# B0_DC12_DC51_1.net
KiCad netlist of a schematic drawn in EAGLE
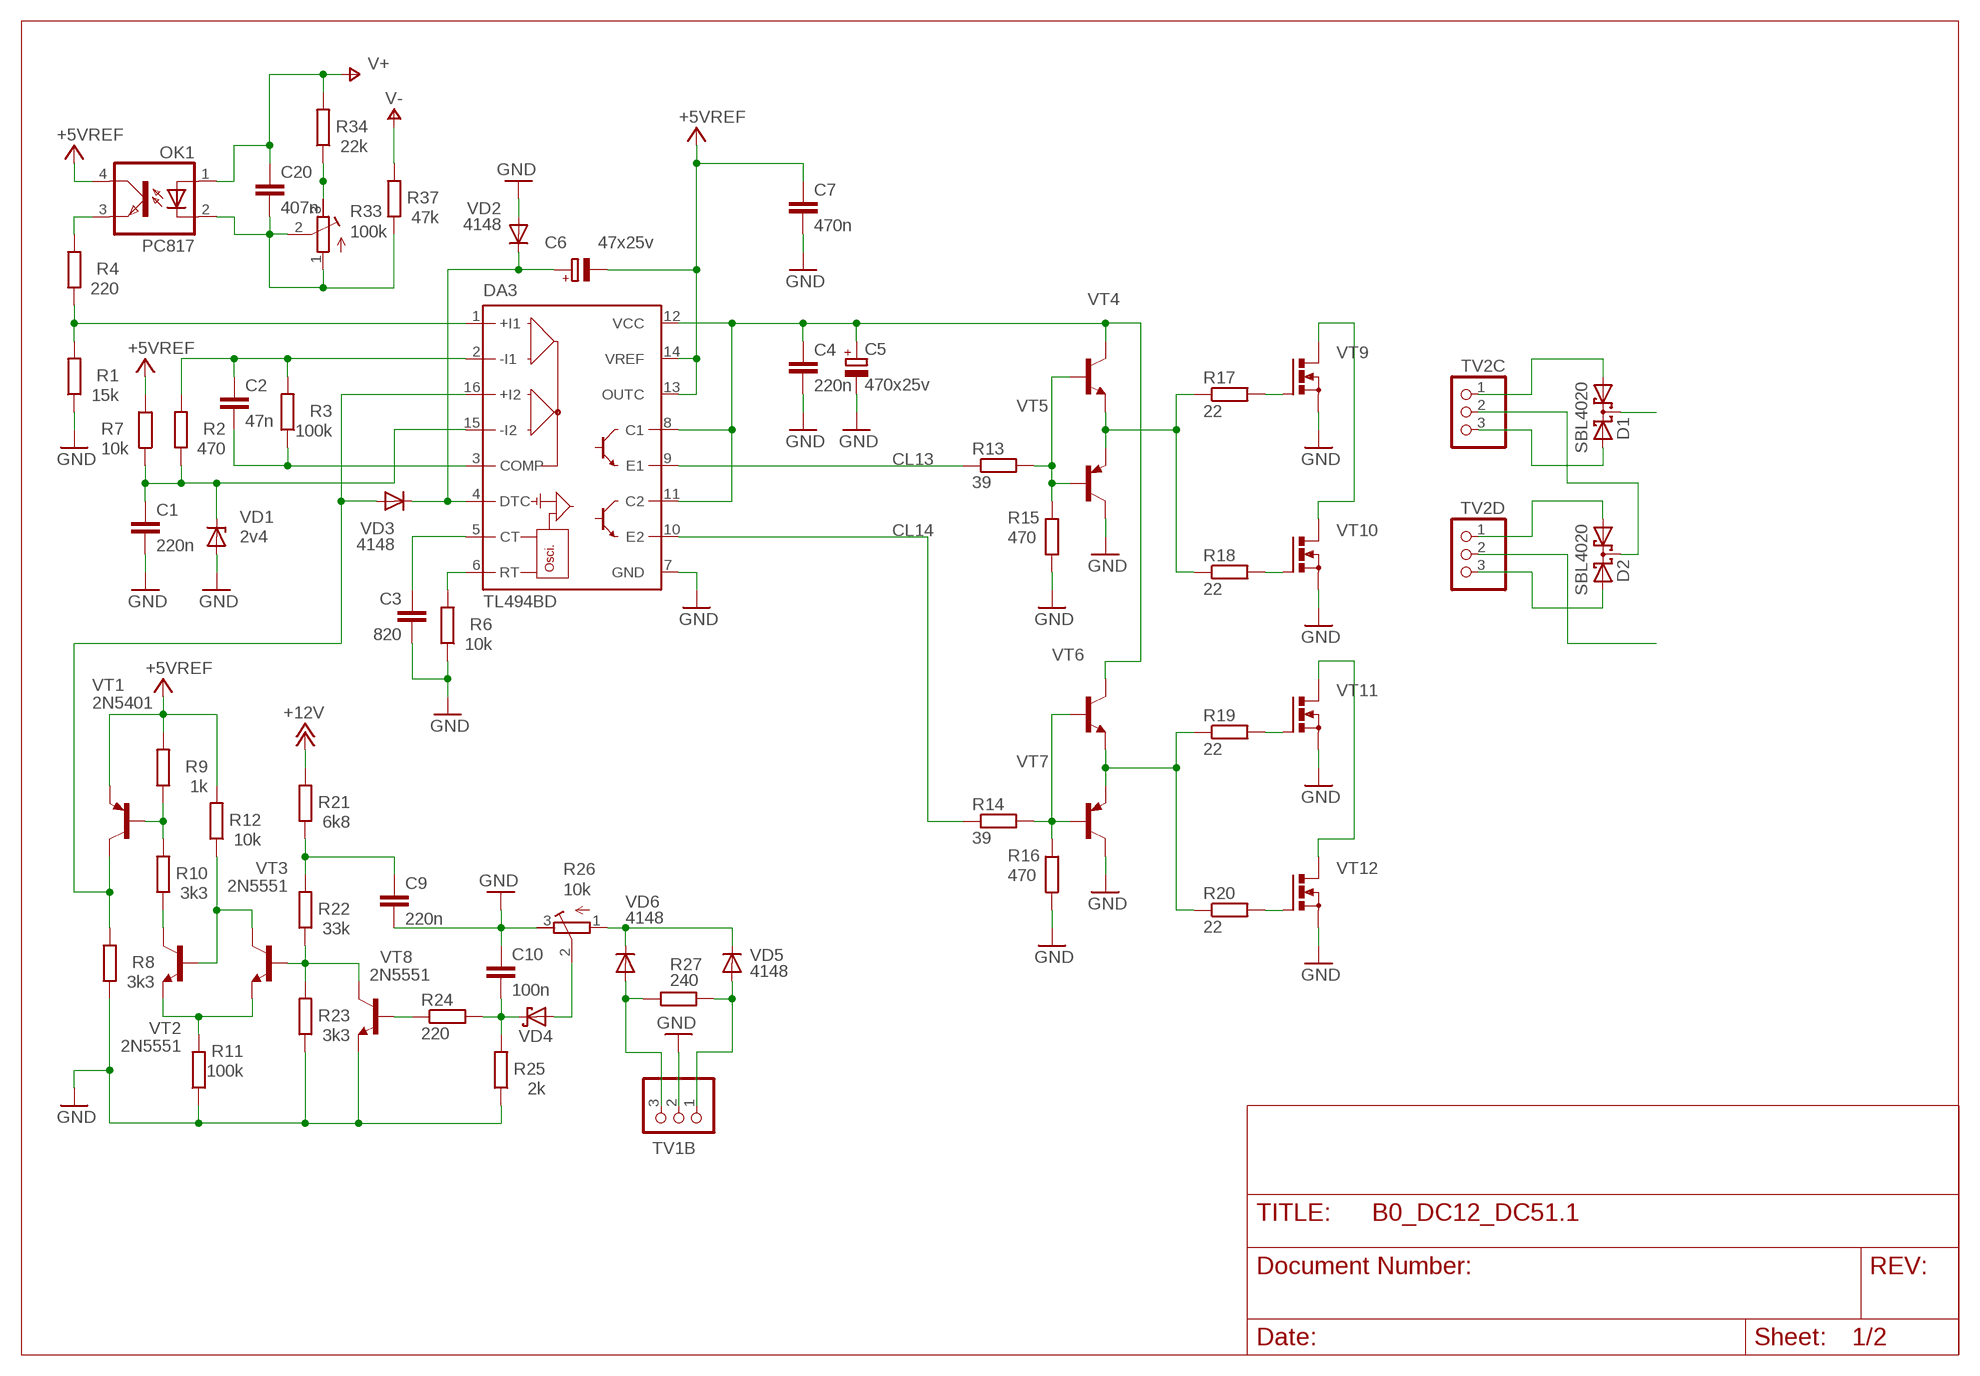
[diagram p0: schematic, sheet 1]
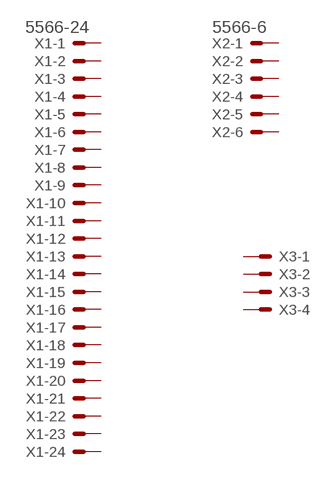
[diagram p1: schematic, sheet 2]

(export (version "E")
  (design (tool "Eeschema 10.0.6"))
  (components
    (comp (ref "X1")
      (value "5566-24")
      (footprint "eagle-import:5566-24")
      (libsource (lib "eagle-import") (part "5566-24"))
    )
    (comp (ref "X2")
      (value "5566-6")
      (footprint "eagle-import:5566-6")
      (fields (field (name "MPN") "95566-61002"))
      (libsource (lib "eagle-import") (part "5566-6"))
    )
    (comp (ref "X3")
      (value "KK-156-4")
      (footprint "eagle-import:KK-156-4")
      (libsource (lib "eagle-import") (part "KK-156-4"))
    )
    (comp (ref "C1")
      (value "220n")
      (footprint "eagle-import:C0805")
      (libsource (lib "eagle-import") (part "C-EUC0805"))
    )
    (comp (ref "C2")
      (value "47n")
      (footprint "eagle-import:C0805")
      (libsource (lib "eagle-import") (part "C-EUC0805"))
    )
    (comp (ref "C3")
      (value "820")
      (footprint "eagle-import:C025-025X050")
      (libsource (lib "eagle-import") (part "C-EU025-025X050"))
    )
    (comp (ref "C4")
      (value "220n")
      (footprint "eagle-import:C0805")
      (libsource (lib "eagle-import") (part "C-EUC0805"))
    )
    (comp (ref "C5")
      (value "470x25v")
      (footprint "eagle-import:E5-10,5")
      (libsource (lib "eagle-import") (part "CPOL-EUE5-10.5"))
    )
    (comp (ref "C6")
      (value "47x25v")
      (footprint "eagle-import:E5-10,5")
      (libsource (lib "eagle-import") (part "CPOL-EUE5-10.5"))
    )
    (comp (ref "C7")
      (value "470n")
      (footprint "eagle-import:C0805")
      (libsource (lib "eagle-import") (part "C-EUC0805"))
    )
    (comp (ref "C9")
      (value "220n")
      (footprint "eagle-import:C0805")
      (libsource (lib "eagle-import") (part "C-EUC0805"))
    )
    (comp (ref "C10")
      (value "100n")
      (footprint "eagle-import:C0805")
      (libsource (lib "eagle-import") (part "C-EUC0805"))
    )
    (comp (ref "C20")
      (value "407n")
      (footprint "eagle-import:C0805")
      (libsource (lib "eagle-import") (part "C-EUC0805"))
    )
    (comp (ref "D1")
      (value "SBL4020")
      (footprint "eagle-import:TO247H")
      (libsource (lib "eagle-import") (part "SCHOTTKY_DUALTO247H"))
    )
    (comp (ref "D2")
      (value "SBL4020")
      (footprint "eagle-import:TO247H")
      (libsource (lib "eagle-import") (part "SCHOTTKY_DUALTO247H"))
    )
    (comp (ref "DA3")
      (value "TL494BD")
      (footprint "eagle-import:SO16")
      (libsource (lib "eagle-import") (part "TL494DB"))
    )
    (comp (ref "OK1")
      (value "PC817")
      (footprint "eagle-import:DIL04")
      (fields (field (name "MPN") "PC817X4J000F"))
      (libsource (lib "eagle-import") (part "PC817"))
    )
    (comp (ref "R1")
      (value "15k")
      (footprint "eagle-import:M0805")
      (libsource (lib "eagle-import") (part "R-EU_M0805"))
    )
    (comp (ref "R2")
      (value "470")
      (footprint "eagle-import:M0805")
      (libsource (lib "eagle-import") (part "R-EU_M0805"))
    )
    (comp (ref "R3")
      (value "100k")
      (footprint "eagle-import:R0805")
      (libsource (lib "eagle-import") (part "R-EU_R0805"))
    )
    (comp (ref "R4")
      (value "220")
      (footprint "eagle-import:M0805")
      (libsource (lib "eagle-import") (part "R-EU_M0805"))
    )
    (comp (ref "R6")
      (value "10k")
      (footprint "eagle-import:0207_12")
      (libsource (lib "eagle-import") (part "R-EU_0207/12"))
    )
    (comp (ref "R7")
      (value "10k")
      (footprint "eagle-import:M0805")
      (libsource (lib "eagle-import") (part "R-EU_M0805"))
    )
    (comp (ref "R8")
      (value "3k3")
      (footprint "eagle-import:M0805")
      (libsource (lib "eagle-import") (part "R-EU_M0805"))
    )
    (comp (ref "R9")
      (value "1k")
      (footprint "eagle-import:M0805")
      (libsource (lib "eagle-import") (part "R-EU_M0805"))
    )
    (comp (ref "R10")
      (value "3k3")
      (footprint "eagle-import:M0805")
      (libsource (lib "eagle-import") (part "R-EU_M0805"))
    )
    (comp (ref "R11")
      (value "100k")
      (footprint "eagle-import:M0805")
      (libsource (lib "eagle-import") (part "R-EU_M0805"))
    )
    (comp (ref "R12")
      (value "10k")
      (footprint "eagle-import:M0805")
      (libsource (lib "eagle-import") (part "R-EU_M0805"))
    )
    (comp (ref "R13")
      (value "39")
      (footprint "eagle-import:M0805")
      (libsource (lib "eagle-import") (part "R-EU_M0805"))
    )
    (comp (ref "R14")
      (value "39")
      (footprint "eagle-import:M0805")
      (libsource (lib "eagle-import") (part "R-EU_M0805"))
    )
    (comp (ref "R15")
      (value "470")
      (footprint "eagle-import:M0805")
      (libsource (lib "eagle-import") (part "R-EU_M0805"))
    )
    (comp (ref "R16")
      (value "470")
      (footprint "eagle-import:M0805")
      (libsource (lib "eagle-import") (part "R-EU_M0805"))
    )
    (comp (ref "R17")
      (value "22")
      (footprint "eagle-import:M0805")
      (libsource (lib "eagle-import") (part "R-EU_M0805"))
    )
    (comp (ref "R18")
      (value "22")
      (footprint "eagle-import:M0805")
      (libsource (lib "eagle-import") (part "R-EU_M0805"))
    )
    (comp (ref "R19")
      (value "22")
      (footprint "eagle-import:M0805")
      (libsource (lib "eagle-import") (part "R-EU_M0805"))
    )
    (comp (ref "R20")
      (value "22")
      (footprint "eagle-import:M0805")
      (libsource (lib "eagle-import") (part "R-EU_M0805"))
    )
    (comp (ref "R21")
      (value "6k8")
      (footprint "eagle-import:M0805")
      (libsource (lib "eagle-import") (part "R-EU_M0805"))
    )
    (comp (ref "R22")
      (value "33k")
      (footprint "eagle-import:M0805")
      (libsource (lib "eagle-import") (part "R-EU_M0805"))
    )
    (comp (ref "R23")
      (value "3k3")
      (footprint "eagle-import:M0805")
      (libsource (lib "eagle-import") (part "R-EU_M0805"))
    )
    (comp (ref "R24")
      (value "220")
      (footprint "eagle-import:M0805")
      (libsource (lib "eagle-import") (part "R-EU_M0805"))
    )
    (comp (ref "R25")
      (value "2k")
      (footprint "eagle-import:M0805")
      (libsource (lib "eagle-import") (part "R-EU_M0805"))
    )
    (comp (ref "R26")
      (value "10k")
      (footprint "eagle-import:RTRIM3296W")
      (libsource (lib "eagle-import") (part "R-TRIMM3296W"))
    )
    (comp (ref "R27")
      (value "240")
      (footprint "eagle-import:0207_10")
      (libsource (lib "eagle-import") (part "R-EU_0207/10"))
    )
    (comp (ref "R33")
      (value "100k")
      (footprint "eagle-import:RTRIM3296W")
      (libsource (lib "eagle-import") (part "R-TRIMM3296W"))
    )
    (comp (ref "R34")
      (value "22k")
      (footprint "eagle-import:M0805")
      (libsource (lib "eagle-import") (part "R-EU_M0805"))
    )
    (comp (ref "R37")
      (value "47k")
      (footprint "eagle-import:M0805")
      (libsource (lib "eagle-import") (part "R-EU_M0805"))
    )
    (comp (ref "TV1B")
      (value "PINHD-1X3")
      (footprint "eagle-import:1X03")
      (libsource (lib "eagle-import") (part "PINHD-1X3"))
    )
    (comp (ref "TV2C")
      (value "PINHD-1X3")
      (footprint "eagle-import:1X03")
      (libsource (lib "eagle-import") (part "PINHD-1X3"))
    )
    (comp (ref "TV2D")
      (value "PINHD-1X3")
      (footprint "eagle-import:1X03")
      (libsource (lib "eagle-import") (part "PINHD-1X3"))
    )
    (comp (ref "VD1")
      (value "2v4")
      (footprint "eagle-import:SOD80C")
      (libsource (lib "eagle-import") (part "ZENER-DIODESOD80C"))
    )
    (comp (ref "VD2")
      (value "4148")
      (footprint "eagle-import:SOD80C")
      (libsource (lib "eagle-import") (part "DIODE-SOD80C"))
    )
    (comp (ref "VD3")
      (value "4148")
      (footprint "eagle-import:SOD80C")
      (libsource (lib "eagle-import") (part "DIODE-SOD80C"))
    )
    (comp (ref "VD4")
      (value "1N5817-B")
      (footprint "eagle-import:DO41-7.6")
      (libsource (lib "eagle-import") (part "1N5817-B"))
    )
    (comp (ref "VD5")
      (value "4148")
      (footprint "eagle-import:SOD80C")
      (libsource (lib "eagle-import") (part "DIODE-SOD80C"))
    )
    (comp (ref "VD6")
      (value "4148")
      (footprint "eagle-import:SOD80C")
      (libsource (lib "eagle-import") (part "DIODE-SOD80C"))
    )
    (comp (ref "VT1")
      (value "2N5401")
      (footprint "eagle-import:TO92")
      (libsource (lib "eagle-import") (part "BJT_PNP_TO-92_ECB"))
    )
    (comp (ref "VT2")
      (value "2N5551")
      (footprint "eagle-import:TO92")
      (libsource (lib "eagle-import") (part "BJT_NPN_TO-92_ECB"))
    )
    (comp (ref "VT3")
      (value "2N5551")
      (footprint "eagle-import:TO92")
      (libsource (lib "eagle-import") (part "BJT_NPN_TO-92_ECB"))
    )
    (comp (ref "VT4")
      (value "-NPN-TO126V")
      (footprint "eagle-import:TO126V")
      (libsource (lib "eagle-import") (part "-NPN-TO126V"))
    )
    (comp (ref "VT5")
      (value "-PNP-TO126V")
      (footprint "eagle-import:TO126V")
      (libsource (lib "eagle-import") (part "-PNP-TO126V"))
    )
    (comp (ref "VT6")
      (value "-NPN-TO126V")
      (footprint "eagle-import:TO126V")
      (libsource (lib "eagle-import") (part "-NPN-TO126V"))
    )
    (comp (ref "VT7")
      (value "-PNP-TO126V")
      (footprint "eagle-import:TO126V")
      (libsource (lib "eagle-import") (part "-PNP-TO126V"))
    )
    (comp (ref "VT8")
      (value "2N5551")
      (footprint "eagle-import:TO92")
      (libsource (lib "eagle-import") (part "BJT_NPN_TO-92_ECB"))
    )
    (comp (ref "VT9")
      (value "MOSFET-N_DPACK")
      (footprint "eagle-import:DPACK")
      (libsource (lib "eagle-import") (part "MOSFET-N_DPACK"))
    )
    (comp (ref "VT10")
      (value "MOSFET-N_DPACK")
      (footprint "eagle-import:DPACK")
      (libsource (lib "eagle-import") (part "MOSFET-N_DPACK"))
    )
    (comp (ref "VT11")
      (value "MOSFET-N_DPACK")
      (footprint "eagle-import:DPACK")
      (libsource (lib "eagle-import") (part "MOSFET-N_DPACK"))
    )
    (comp (ref "VT12")
      (value "MOSFET-N_DPACK")
      (footprint "eagle-import:DPACK")
      (libsource (lib "eagle-import") (part "MOSFET-N_DPACK"))
    )
  )
  (nets
    (net (code "1") (name "+5VREF") (class "Default")
      (node (ref "C6") (pin "-") (pinfunction "-_-") (pintype "passive"))
      (node (ref "C7") (pin "1") (pinfunction "1_1") (pintype "passive"))
      (node (ref "DA3") (pin "13") (pinfunction "OUTC_13") (pintype "output"))
      (node (ref "DA3") (pin "14") (pinfunction "VREF_14") (pintype "input"))
      (node (ref "OK1") (pin "4") (pinfunction "COL_4") (pintype "passive"))
      (node (ref "R12") (pin "2") (pinfunction "2_2") (pintype "passive"))
      (node (ref "R7") (pin "2") (pinfunction "2_2") (pintype "passive"))
      (node (ref "R9") (pin "2") (pinfunction "2_2") (pintype "passive"))
      (node (ref "VT1") (pin "1") (pinfunction "E_1") (pintype "passive"))
    )
    (net (code "2") (name "+12V") (class "Default")
      (node (ref "R21") (pin "2") (pinfunction "2_2") (pintype "passive"))
    )
    (net (code "3") (name "CL13") (class "Default")
      (node (ref "DA3") (pin "9") (pinfunction "E1_9") (pintype "passive"))
      (node (ref "R13") (pin "1") (pinfunction "1_1") (pintype "passive"))
    )
    (net (code "4") (name "CL14") (class "Default")
      (node (ref "DA3") (pin "10") (pinfunction "E2_10") (pintype "passive"))
      (node (ref "R14") (pin "1") (pinfunction "1_1") (pintype "passive"))
    )
    (net (code "5") (name "GND") (class "Default")
      (node (ref "C1") (pin "2") (pinfunction "2_2") (pintype "passive"))
      (node (ref "C10") (pin "1") (pinfunction "1_1") (pintype "passive"))
      (node (ref "C3") (pin "2") (pinfunction "2_2") (pintype "passive"))
      (node (ref "C4") (pin "2") (pinfunction "2_2") (pintype "passive"))
      (node (ref "C5") (pin "-") (pinfunction "-_-") (pintype "passive"))
      (node (ref "C7") (pin "2") (pinfunction "2_2") (pintype "passive"))
      (node (ref "C9") (pin "2") (pinfunction "2_2") (pintype "passive"))
      (node (ref "DA3") (pin "7") (pinfunction "GND_7") (pintype "power_in"))
      (node (ref "R1") (pin "1") (pinfunction "1_1") (pintype "passive"))
      (node (ref "R11") (pin "1") (pinfunction "1_1") (pintype "passive"))
      (node (ref "R15") (pin "1") (pinfunction "1_1") (pintype "passive"))
      (node (ref "R16") (pin "1") (pinfunction "1_1") (pintype "passive"))
      (node (ref "R23") (pin "1") (pinfunction "1_1") (pintype "passive"))
      (node (ref "R25") (pin "1") (pinfunction "1_1") (pintype "passive"))
      (node (ref "R26") (pin "3") (pinfunction "E_3") (pintype "passive"))
      (node (ref "R6") (pin "1") (pinfunction "1_1") (pintype "passive"))
      (node (ref "R8") (pin "1") (pinfunction "1_1") (pintype "passive"))
      (node (ref "TV1B") (pin "2") (pinfunction "2_2") (pintype "passive"))
      (node (ref "VD1") (pin "A") (pinfunction "A_A") (pintype "passive"))
      (node (ref "VD2") (pin "A") (pinfunction "A_A") (pintype "passive"))
      (node (ref "VT10") (pin "S") (pinfunction "S_S") (pintype "passive"))
      (node (ref "VT11") (pin "S") (pinfunction "S_S") (pintype "passive"))
      (node (ref "VT12") (pin "S") (pinfunction "S_S") (pintype "passive"))
      (node (ref "VT5") (pin "2") (pinfunction "C_2") (pintype "passive"))
      (node (ref "VT7") (pin "2") (pinfunction "C_2") (pintype "passive"))
      (node (ref "VT8") (pin "1") (pinfunction "E_1") (pintype "passive"))
      (node (ref "VT9") (pin "S") (pinfunction "S_S") (pintype "passive"))
    )
    (net (code "6") (name "Net-(C9-Pad1)") (class "Default")
      (node (ref "C9") (pin "1") (pinfunction "1_1") (pintype "passive"))
      (node (ref "R21") (pin "1") (pinfunction "1_1") (pintype "passive"))
      (node (ref "R22") (pin "2") (pinfunction "2_2") (pintype "passive"))
    )
    (net (code "7") (name "Net-(C10-Pad2)") (class "Default")
      (node (ref "C10") (pin "2") (pinfunction "2_2") (pintype "passive"))
      (node (ref "R24") (pin "2") (pinfunction "2_2") (pintype "passive"))
      (node (ref "R25") (pin "2") (pinfunction "2_2") (pintype "passive"))
      (node (ref "VD4") (pin "C") (pinfunction "C_C") (pintype "passive"))
    )
    (net (code "8") (name "Net-(D1-A1)") (class "Default")
      (node (ref "D1") (pin "1") (pinfunction "A1_1") (pintype "passive"))
      (node (ref "TV2C") (pin "1") (pinfunction "1_1") (pintype "passive"))
    )
    (net (code "9") (name "Net-(D1-A2)") (class "Default")
      (node (ref "D1") (pin "3") (pinfunction "A2_3") (pintype "passive"))
      (node (ref "TV2C") (pin "3") (pinfunction "3_3") (pintype "passive"))
    )
    (net (code "10") (name "Net-(D2-A1)") (class "Default")
      (node (ref "D2") (pin "1") (pinfunction "A1_1") (pintype "passive"))
      (node (ref "TV2D") (pin "1") (pinfunction "1_1") (pintype "passive"))
    )
    (net (code "11") (name "Net-(D2-A2)") (class "Default")
      (node (ref "D2") (pin "3") (pinfunction "A2_3") (pintype "passive"))
      (node (ref "TV2D") (pin "3") (pinfunction "3_3") (pintype "passive"))
    )
    (net (code "12") (name "Net-(D2-C)") (class "Default")
      (node (ref "D2") (pin "2") (pinfunction "C_2") (pintype "passive"))
      (node (ref "TV2C") (pin "2") (pinfunction "2_2") (pintype "passive"))
    )
    (net (code "13") (name "Net-(DA3-+I1)") (class "Default")
      (node (ref "DA3") (pin "1") (pinfunction "+I1_1") (pintype "input"))
      (node (ref "R1") (pin "2") (pinfunction "2_2") (pintype "passive"))
      (node (ref "R4") (pin "1") (pinfunction "1_1") (pintype "passive"))
    )
    (net (code "14") (name "Net-(DA3-+I2)") (class "Default")
      (node (ref "DA3") (pin "16") (pinfunction "+I2_16") (pintype "input"))
      (node (ref "R8") (pin "2") (pinfunction "2_2") (pintype "passive"))
      (node (ref "VD3") (pin "A") (pinfunction "A_A") (pintype "passive"))
      (node (ref "VT1") (pin "2") (pinfunction "C_2") (pintype "passive"))
    )
    (net (code "15") (name "Net-(DA3--I1)") (class "Default")
      (node (ref "C2") (pin "1") (pinfunction "1_1") (pintype "passive"))
      (node (ref "DA3") (pin "2") (pinfunction "-I1_2") (pintype "input"))
      (node (ref "R2") (pin "2") (pinfunction "2_2") (pintype "passive"))
      (node (ref "R3") (pin "2") (pinfunction "2_2") (pintype "passive"))
    )
    (net (code "16") (name "Net-(DA3--I2)") (class "Default")
      (node (ref "C1") (pin "1") (pinfunction "1_1") (pintype "passive"))
      (node (ref "DA3") (pin "15") (pinfunction "-I2_15") (pintype "input"))
      (node (ref "R2") (pin "1") (pinfunction "1_1") (pintype "passive"))
      (node (ref "R7") (pin "1") (pinfunction "1_1") (pintype "passive"))
      (node (ref "VD1") (pin "C") (pinfunction "C_C") (pintype "passive"))
    )
    (net (code "17") (name "Net-(DA3-C1)") (class "Default")
      (node (ref "C4") (pin "1") (pinfunction "1_1") (pintype "passive"))
      (node (ref "C5") (pin "+") (pinfunction "+_+") (pintype "passive"))
      (node (ref "DA3") (pin "11") (pinfunction "C2_11") (pintype "passive"))
      (node (ref "DA3") (pin "12") (pinfunction "VCC_12") (pintype "power_in"))
      (node (ref "DA3") (pin "8") (pinfunction "C1_8") (pintype "passive"))
      (node (ref "VT4") (pin "2") (pinfunction "C_2") (pintype "passive"))
      (node (ref "VT6") (pin "2") (pinfunction "C_2") (pintype "passive"))
    )
    (net (code "18") (name "Net-(DA3-COMP)") (class "Default")
      (node (ref "C2") (pin "2") (pinfunction "2_2") (pintype "passive"))
      (node (ref "DA3") (pin "3") (pinfunction "COMP_3") (pintype "passive"))
      (node (ref "R3") (pin "1") (pinfunction "1_1") (pintype "passive"))
    )
    (net (code "19") (name "Net-(DA3-CT)") (class "Default")
      (node (ref "C3") (pin "1") (pinfunction "1_1") (pintype "passive"))
      (node (ref "DA3") (pin "5") (pinfunction "CT_5") (pintype "input"))
    )
    (net (code "20") (name "Net-(DA3-DTC)") (class "Default")
      (node (ref "C6") (pin "+") (pinfunction "+_+") (pintype "passive"))
      (node (ref "DA3") (pin "4") (pinfunction "DTC_4") (pintype "input"))
      (node (ref "VD2") (pin "C") (pinfunction "C_C") (pintype "passive"))
      (node (ref "VD3") (pin "C") (pinfunction "C_C") (pintype "passive"))
    )
    (net (code "21") (name "Net-(DA3-RT)") (class "Default")
      (node (ref "DA3") (pin "6") (pinfunction "RT_6") (pintype "input"))
      (node (ref "R6") (pin "2") (pinfunction "2_2") (pintype "passive"))
    )
    (net (code "22") (name "Net-(OK1-C)") (class "Default")
      (node (ref "C20") (pin "2") (pinfunction "2_2") (pintype "passive"))
      (node (ref "OK1") (pin "2") (pinfunction "C_2") (pintype "passive"))
      (node (ref "R33") (pin "1") (pinfunction "A_1") (pintype "passive"))
      (node (ref "R33") (pin "2") (pinfunction "S_2") (pintype "passive"))
      (node (ref "R37") (pin "1") (pinfunction "1_1") (pintype "passive"))
    )
    (net (code "23") (name "Net-(OK1-EMIT)") (class "Default")
      (node (ref "OK1") (pin "3") (pinfunction "EMIT_3") (pintype "passive"))
      (node (ref "R4") (pin "2") (pinfunction "2_2") (pintype "passive"))
    )
    (net (code "24") (name "Net-(R17-Pad2)") (class "Default")
      (node (ref "R17") (pin "2") (pinfunction "2_2") (pintype "passive"))
      (node (ref "VT9") (pin "G") (pinfunction "G_G") (pintype "passive"))
    )
    (net (code "25") (name "Net-(R18-Pad2)") (class "Default")
      (node (ref "R18") (pin "2") (pinfunction "2_2") (pintype "passive"))
      (node (ref "VT10") (pin "G") (pinfunction "G_G") (pintype "passive"))
    )
    (net (code "26") (name "Net-(R19-Pad2)") (class "Default")
      (node (ref "R19") (pin "2") (pinfunction "2_2") (pintype "passive"))
      (node (ref "VT11") (pin "G") (pinfunction "G_G") (pintype "passive"))
    )
    (net (code "27") (name "Net-(R20-Pad2)") (class "Default")
      (node (ref "R20") (pin "2") (pinfunction "2_2") (pintype "passive"))
      (node (ref "VT12") (pin "G") (pinfunction "G_G") (pintype "passive"))
    )
    (net (code "28") (name "Net-(R26-A)") (class "Default")
      (node (ref "R26") (pin "1") (pinfunction "A_1") (pintype "passive"))
      (node (ref "VD5") (pin "C") (pinfunction "C_C") (pintype "passive"))
      (node (ref "VD6") (pin "C") (pinfunction "C_C") (pintype "passive"))
    )
    (net (code "29") (name "Net-(R26-S)") (class "Default")
      (node (ref "R26") (pin "2") (pinfunction "S_2") (pintype "passive"))
      (node (ref "VD4") (pin "A") (pinfunction "A_A") (pintype "passive"))
    )
    (net (code "30") (name "Net-(R27-Pad1)") (class "Default")
      (node (ref "R27") (pin "1") (pinfunction "1_1") (pintype "passive"))
      (node (ref "TV1B") (pin "3") (pinfunction "3_3") (pintype "passive"))
      (node (ref "VD6") (pin "A") (pinfunction "A_A") (pintype "passive"))
    )
    (net (code "31") (name "Net-(R27-Pad2)") (class "Default")
      (node (ref "R27") (pin "2") (pinfunction "2_2") (pintype "passive"))
      (node (ref "TV1B") (pin "1") (pinfunction "1_1") (pintype "passive"))
      (node (ref "VD5") (pin "A") (pinfunction "A_A") (pintype "passive"))
    )
    (net (code "32") (name "Net-(R33-E)") (class "Default")
      (node (ref "R33") (pin "3") (pinfunction "E_3") (pintype "passive"))
      (node (ref "R34") (pin "1") (pinfunction "1_1") (pintype "passive"))
    )
    (net (code "33") (name "Net-(VT1-B)") (class "Default")
      (node (ref "R10") (pin "2") (pinfunction "2_2") (pintype "passive"))
      (node (ref "R9") (pin "1") (pinfunction "1_1") (pintype "passive"))
      (node (ref "VT1") (pin "3") (pinfunction "B_3") (pintype "passive"))
    )
    (net (code "34") (name "Net-(VT2-B)") (class "Default")
      (node (ref "R12") (pin "1") (pinfunction "1_1") (pintype "passive"))
      (node (ref "VT2") (pin "3") (pinfunction "B_3") (pintype "passive"))
      (node (ref "VT3") (pin "2") (pinfunction "C_2") (pintype "passive"))
    )
    (net (code "35") (name "Net-(VT2-C)") (class "Default")
      (node (ref "R10") (pin "1") (pinfunction "1_1") (pintype "passive"))
      (node (ref "VT2") (pin "2") (pinfunction "C_2") (pintype "passive"))
    )
    (net (code "36") (name "Net-(VT2-E)") (class "Default")
      (node (ref "R11") (pin "2") (pinfunction "2_2") (pintype "passive"))
      (node (ref "VT2") (pin "1") (pinfunction "E_1") (pintype "passive"))
      (node (ref "VT3") (pin "1") (pinfunction "E_1") (pintype "passive"))
    )
    (net (code "37") (name "Net-(VT3-B)") (class "Default")
      (node (ref "R22") (pin "1") (pinfunction "1_1") (pintype "passive"))
      (node (ref "R23") (pin "2") (pinfunction "2_2") (pintype "passive"))
      (node (ref "VT3") (pin "3") (pinfunction "B_3") (pintype "passive"))
      (node (ref "VT8") (pin "2") (pinfunction "C_2") (pintype "passive"))
    )
    (net (code "38") (name "Net-(VT4-B)") (class "Default")
      (node (ref "R13") (pin "2") (pinfunction "2_2") (pintype "passive"))
      (node (ref "R15") (pin "2") (pinfunction "2_2") (pintype "passive"))
      (node (ref "VT4") (pin "3") (pinfunction "B_3") (pintype "passive"))
      (node (ref "VT5") (pin "3") (pinfunction "B_3") (pintype "passive"))
    )
    (net (code "39") (name "Net-(VT4-E)") (class "Default")
      (node (ref "R17") (pin "1") (pinfunction "1_1") (pintype "passive"))
      (node (ref "R18") (pin "1") (pinfunction "1_1") (pintype "passive"))
      (node (ref "VT4") (pin "1") (pinfunction "E_1") (pintype "passive"))
      (node (ref "VT5") (pin "1") (pinfunction "E_1") (pintype "passive"))
    )
    (net (code "40") (name "Net-(VT6-B)") (class "Default")
      (node (ref "R14") (pin "2") (pinfunction "2_2") (pintype "passive"))
      (node (ref "R16") (pin "2") (pinfunction "2_2") (pintype "passive"))
      (node (ref "VT6") (pin "3") (pinfunction "B_3") (pintype "passive"))
      (node (ref "VT7") (pin "3") (pinfunction "B_3") (pintype "passive"))
    )
    (net (code "41") (name "Net-(VT6-E)") (class "Default")
      (node (ref "R19") (pin "1") (pinfunction "1_1") (pintype "passive"))
      (node (ref "R20") (pin "1") (pinfunction "1_1") (pintype "passive"))
      (node (ref "VT6") (pin "1") (pinfunction "E_1") (pintype "passive"))
      (node (ref "VT7") (pin "1") (pinfunction "E_1") (pintype "passive"))
    )
    (net (code "42") (name "Net-(VT8-B)") (class "Default")
      (node (ref "R24") (pin "1") (pinfunction "1_1") (pintype "passive"))
      (node (ref "VT8") (pin "3") (pinfunction "B_3") (pintype "passive"))
    )
    (net (code "43") (name "Net-(VT10-PadD)") (class "Default")
      (node (ref "VT10") (pin "D") (pinfunction "D_D") (pintype "passive"))
      (node (ref "VT9") (pin "D") (pinfunction "D_D") (pintype "passive"))
    )
    (net (code "44") (name "Net-(VT11-PadD)") (class "Default")
      (node (ref "VT11") (pin "D") (pinfunction "D_D") (pintype "passive"))
      (node (ref "VT12") (pin "D") (pinfunction "D_D") (pintype "passive"))
    )
    (net (code "45") (name "V+") (class "Default")
      (node (ref "C20") (pin "1") (pinfunction "1_1") (pintype "passive"))
      (node (ref "OK1") (pin "1") (pinfunction "A_1") (pintype "passive"))
      (node (ref "R34") (pin "2") (pinfunction "2_2") (pintype "passive"))
    )
    (net (code "46") (name "V-") (class "Default")
      (node (ref "R37") (pin "2") (pinfunction "2_2") (pintype "passive"))
    )
    (net (code "47") (name "unconnected-(D1-C-Pad2)") (class "Default")
      (node (ref "D1") (pin "2") (pinfunction "C_2") (pintype "passive"))
    )
    (net (code "48") (name "unconnected-(TV2D-Pad2)") (class "Default")
      (node (ref "TV2D") (pin "2") (pinfunction "2_2") (pintype "passive"))
    )
    (net (code "49") (name "unconnected-(X1A-S-Pad1)") (class "Default")
      (node (ref "X1") (pin "1") (pinfunction "S_1") (pintype "passive"))
    )
    (net (code "50") (name "unconnected-(X1B-S-Pad10)") (class "Default")
      (node (ref "X1") (pin "10") (pinfunction "S_10") (pintype "passive"))
    )
    (net (code "51") (name "unconnected-(X1C-S-Pad11)") (class "Default")
      (node (ref "X1") (pin "11") (pinfunction "S_11") (pintype "passive"))
    )
    (net (code "52") (name "unconnected-(X1D-S-Pad12)") (class "Default")
      (node (ref "X1") (pin "12") (pinfunction "S_12") (pintype "passive"))
    )
    (net (code "53") (name "unconnected-(X1E-S-Pad13)") (class "Default")
      (node (ref "X1") (pin "13") (pinfunction "S_13") (pintype "passive"))
    )
    (net (code "54") (name "unconnected-(X1F-S-Pad14)") (class "Default")
      (node (ref "X1") (pin "14") (pinfunction "S_14") (pintype "passive"))
    )
    (net (code "55") (name "unconnected-(X1G-S-Pad15)") (class "Default")
      (node (ref "X1") (pin "15") (pinfunction "S_15") (pintype "passive"))
    )
    (net (code "56") (name "unconnected-(X1H-S-Pad16)") (class "Default")
      (node (ref "X1") (pin "16") (pinfunction "S_16") (pintype "passive"))
    )
    (net (code "57") (name "unconnected-(X1I-S-Pad17)") (class "Default")
      (node (ref "X1") (pin "17") (pinfunction "S_17") (pintype "passive"))
    )
    (net (code "58") (name "unconnected-(X1J-S-Pad18)") (class "Default")
      (node (ref "X1") (pin "18") (pinfunction "S_18") (pintype "passive"))
    )
    (net (code "59") (name "unconnected-(X1K-S-Pad19)") (class "Default")
      (node (ref "X1") (pin "19") (pinfunction "S_19") (pintype "passive"))
    )
    (net (code "60") (name "unconnected-(X1L-S-Pad2)") (class "Default")
      (node (ref "X1") (pin "2") (pinfunction "S_2") (pintype "passive"))
    )
    (net (code "61") (name "unconnected-(X1M-S-Pad20)") (class "Default")
      (node (ref "X1") (pin "20") (pinfunction "S_20") (pintype "passive"))
    )
    (net (code "62") (name "unconnected-(X1N-S-Pad21)") (class "Default")
      (node (ref "X1") (pin "21") (pinfunction "S_21") (pintype "passive"))
    )
    (net (code "63") (name "unconnected-(X1O-S-Pad22)") (class "Default")
      (node (ref "X1") (pin "22") (pinfunction "S_22") (pintype "passive"))
    )
    (net (code "64") (name "unconnected-(X1P-S-Pad23)") (class "Default")
      (node (ref "X1") (pin "23") (pinfunction "S_23") (pintype "passive"))
    )
    (net (code "65") (name "unconnected-(X1Q-S-Pad24)") (class "Default")
      (node (ref "X1") (pin "24") (pinfunction "S_24") (pintype "passive"))
    )
    (net (code "66") (name "unconnected-(X1R-S-Pad3)") (class "Default")
      (node (ref "X1") (pin "3") (pinfunction "S_3") (pintype "passive"))
    )
    (net (code "67") (name "unconnected-(X1S-S-Pad4)") (class "Default")
      (node (ref "X1") (pin "4") (pinfunction "S_4") (pintype "passive"))
    )
    (net (code "68") (name "unconnected-(X1T-S-Pad5)") (class "Default")
      (node (ref "X1") (pin "5") (pinfunction "S_5") (pintype "passive"))
    )
    (net (code "69") (name "unconnected-(X1U-S-Pad6)") (class "Default")
      (node (ref "X1") (pin "6") (pinfunction "S_6") (pintype "passive"))
    )
    (net (code "70") (name "unconnected-(X1V-S-Pad7)") (class "Default")
      (node (ref "X1") (pin "7") (pinfunction "S_7") (pintype "passive"))
    )
    (net (code "71") (name "unconnected-(X1W-S-Pad8)") (class "Default")
      (node (ref "X1") (pin "8") (pinfunction "S_8") (pintype "passive"))
    )
    (net (code "72") (name "unconnected-(X1X-S-Pad9)") (class "Default")
      (node (ref "X1") (pin "9") (pinfunction "S_9") (pintype "passive"))
    )
    (net (code "73") (name "unconnected-(X2A-S-Pad1)") (class "Default")
      (node (ref "X2") (pin "1") (pinfunction "S_1") (pintype "passive"))
    )
    (net (code "74") (name "unconnected-(X2B-S-Pad2)") (class "Default")
      (node (ref "X2") (pin "2") (pinfunction "S_2") (pintype "passive"))
    )
    (net (code "75") (name "unconnected-(X2C-S-Pad3)") (class "Default")
      (node (ref "X2") (pin "3") (pinfunction "S_3") (pintype "passive"))
    )
    (net (code "76") (name "unconnected-(X2D-S-Pad4)") (class "Default")
      (node (ref "X2") (pin "4") (pinfunction "S_4") (pintype "passive"))
    )
    (net (code "77") (name "unconnected-(X2E-S-Pad5)") (class "Default")
      (node (ref "X2") (pin "5") (pinfunction "S_5") (pintype "passive"))
    )
    (net (code "78") (name "unconnected-(X2F-S-Pad6)") (class "Default")
      (node (ref "X2") (pin "6") (pinfunction "S_6") (pintype "passive"))
    )
    (net (code "79") (name "unconnected-(X3A-S-Pad1)") (class "Default")
      (node (ref "X3") (pin "1") (pinfunction "S_1") (pintype "passive"))
    )
    (net (code "80") (name "unconnected-(X3B-S-Pad2)") (class "Default")
      (node (ref "X3") (pin "2") (pinfunction "S_2") (pintype "passive"))
    )
    (net (code "81") (name "unconnected-(X3C-S-Pad3)") (class "Default")
      (node (ref "X3") (pin "3") (pinfunction "S_3") (pintype "passive"))
    )
    (net (code "82") (name "unconnected-(X3D-S-Pad4)") (class "Default")
      (node (ref "X3") (pin "4") (pinfunction "S_4") (pintype "passive"))
    )
  )
)
